# Charger.net
KiCad netlist of a schematic drawn in EAGLE
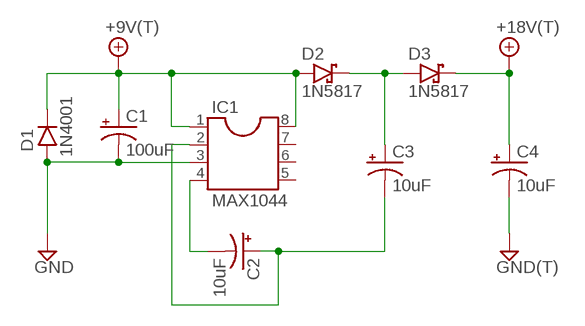
[diagram p0: schematic, sheet 1]

(export (version "E")
  (design (tool "Eeschema 10.0.6"))
  (components
    (comp (ref "+9V")
      (value "+9V(T)")
      (footprint "eagle-import:SQUARE")
      (libsource (lib "eagle-import") (part "+9V(T)"))
    )
    (comp (ref "+18V")
      (value "+18V(T)")
      (footprint "eagle-import:SQUARE")
      (libsource (lib "eagle-import") (part "+18V(T)"))
    )
    (comp (ref "C1")
      (value "100uF")
      (footprint "eagle-import:080_035_1")
      (libsource (lib "eagle-import") (part "0801"))
    )
    (comp (ref "C2")
      (value "10uF")
      (footprint "eagle-import:050_020_1")
      (libsource (lib "eagle-import") (part "0501"))
    )
    (comp (ref "C3")
      (value "10uF")
      (footprint "eagle-import:050_020_1")
      (libsource (lib "eagle-import") (part "0501"))
    )
    (comp (ref "C4")
      (value "10uF")
      (footprint "eagle-import:050_020_1")
      (libsource (lib "eagle-import") (part "0501"))
    )
    (comp (ref "D1")
      (value "1N4001")
      (footprint "eagle-import:DO41-3")
      (libsource (lib "eagle-import") (part "1N400X.3"))
    )
    (comp (ref "D2")
      (value "1N5817")
      (footprint "eagle-import:DO41-3")
      (libsource (lib "eagle-import") (part "1N5817"))
    )
    (comp (ref "D3")
      (value "1N5817")
      (footprint "eagle-import:DO41-3")
      (libsource (lib "eagle-import") (part "1N5817"))
    )
    (comp (ref "GND")
      (value "GND(T)")
      (footprint "eagle-import:SQUARE")
      (libsource (lib "eagle-import") (part "GND(T)"))
    )
    (comp (ref "IC1")
      (value "MAX1044")
      (footprint "eagle-import:DIL08")
      (libsource (lib "eagle-import") (part "MAX1044"))
    )
  )
  (nets
    (net (code "1") (name "+9V(T)") (class "Default")
      (node (ref "+9V") (pin "1") (pinfunction "+9V_1") (pintype "power_in"))
      (node (ref "C1") (pin "+") (pinfunction "+_+") (pintype "passive"))
      (node (ref "D1") (pin "C") (pinfunction "C_C") (pintype "passive"))
      (node (ref "D2") (pin "A") (pinfunction "A_A") (pintype "passive"))
      (node (ref "IC1") (pin "1") (pinfunction "1_1") (pintype "passive"))
      (node (ref "IC1") (pin "8") (pinfunction "8_8") (pintype "passive"))
    )
    (net (code "2") (name "+18V(T)") (class "Default")
      (node (ref "+18V") (pin "1") (pinfunction "+18V_1") (pintype "power_in"))
      (node (ref "C4") (pin "+") (pinfunction "+_+") (pintype "passive"))
      (node (ref "D3") (pin "C") (pinfunction "C_C") (pintype "passive"))
    )
    (net (code "3") (name "GND") (class "Default")
      (node (ref "C1") (pin "-") (pinfunction "-_-") (pintype "passive"))
      (node (ref "C4") (pin "-") (pinfunction "-_-") (pintype "passive"))
      (node (ref "D1") (pin "A") (pinfunction "A_A") (pintype "passive"))
      (node (ref "GND") (pin "1") (pinfunction "GND_1") (pintype "power_in"))
      (node (ref "IC1") (pin "3") (pinfunction "3_3") (pintype "passive"))
    )
    (net (code "4") (name "Net-(C2-Pad+)") (class "Default")
      (node (ref "C2") (pin "+") (pinfunction "+_+") (pintype "passive"))
      (node (ref "C3") (pin "-") (pinfunction "-_-") (pintype "passive"))
      (node (ref "IC1") (pin "2") (pinfunction "2_2") (pintype "passive"))
    )
    (net (code "5") (name "Net-(C2-Pad-)") (class "Default")
      (node (ref "C2") (pin "-") (pinfunction "-_-") (pintype "passive"))
      (node (ref "IC1") (pin "4") (pinfunction "4_4") (pintype "passive"))
    )
    (net (code "6") (name "Net-(C3-Pad+)") (class "Default")
      (node (ref "C3") (pin "+") (pinfunction "+_+") (pintype "passive"))
      (node (ref "D2") (pin "C") (pinfunction "C_C") (pintype "passive"))
      (node (ref "D3") (pin "A") (pinfunction "A_A") (pintype "passive"))
    )
    (net (code "7") (name "unconnected-(IC1-Pad5)") (class "Default")
      (node (ref "IC1") (pin "5") (pinfunction "5_5") (pintype "passive"))
    )
    (net (code "8") (name "unconnected-(IC1-Pad6)") (class "Default")
      (node (ref "IC1") (pin "6") (pinfunction "6_6") (pintype "passive"))
    )
    (net (code "9") (name "unconnected-(IC1-Pad7)") (class "Default")
      (node (ref "IC1") (pin "7") (pinfunction "7_7") (pintype "passive"))
    )
  )
)
